# TeensyLED_15061000.net
KiCad netlist of a schematic drawn in EAGLE
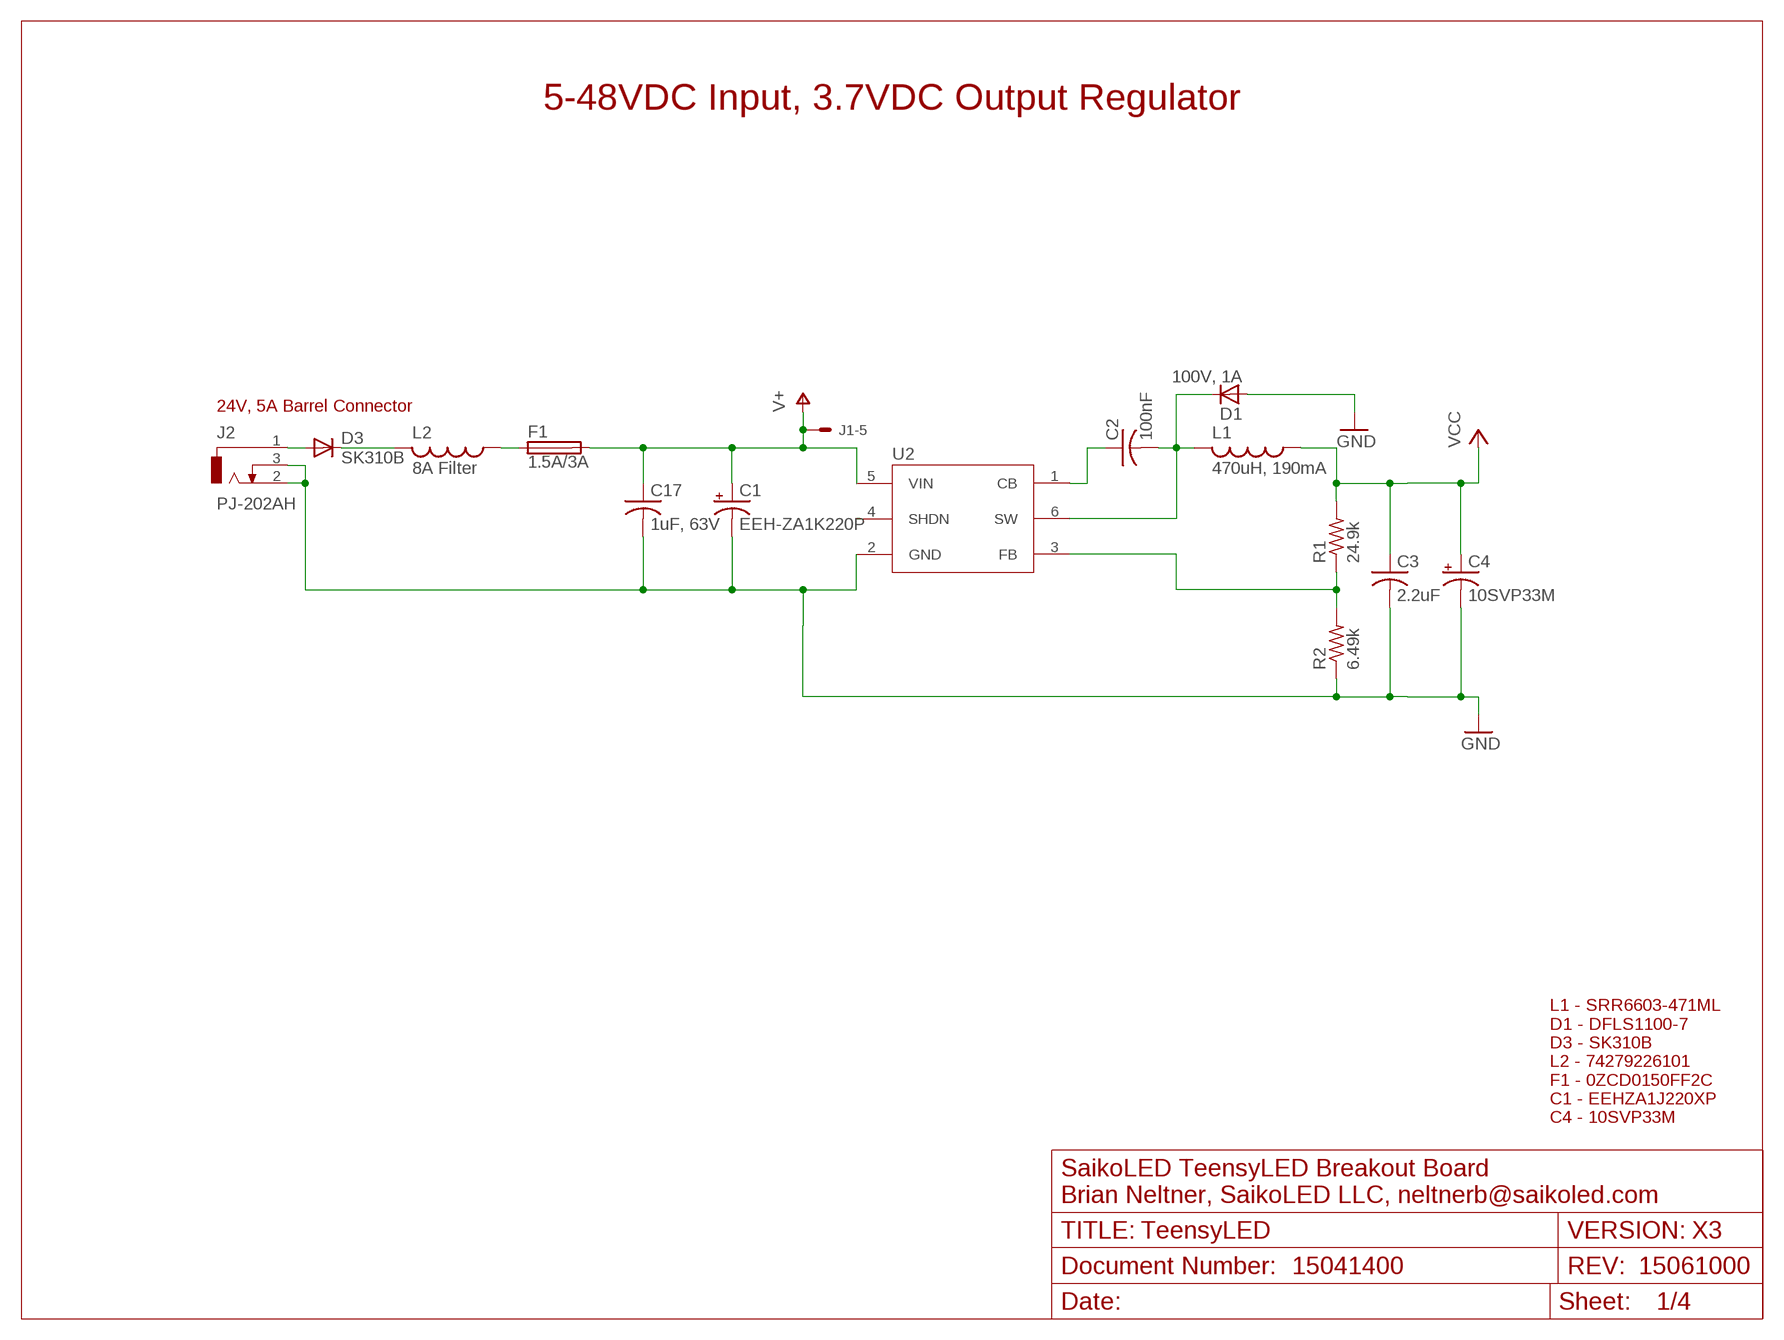
[diagram p0: schematic, sheet 1]
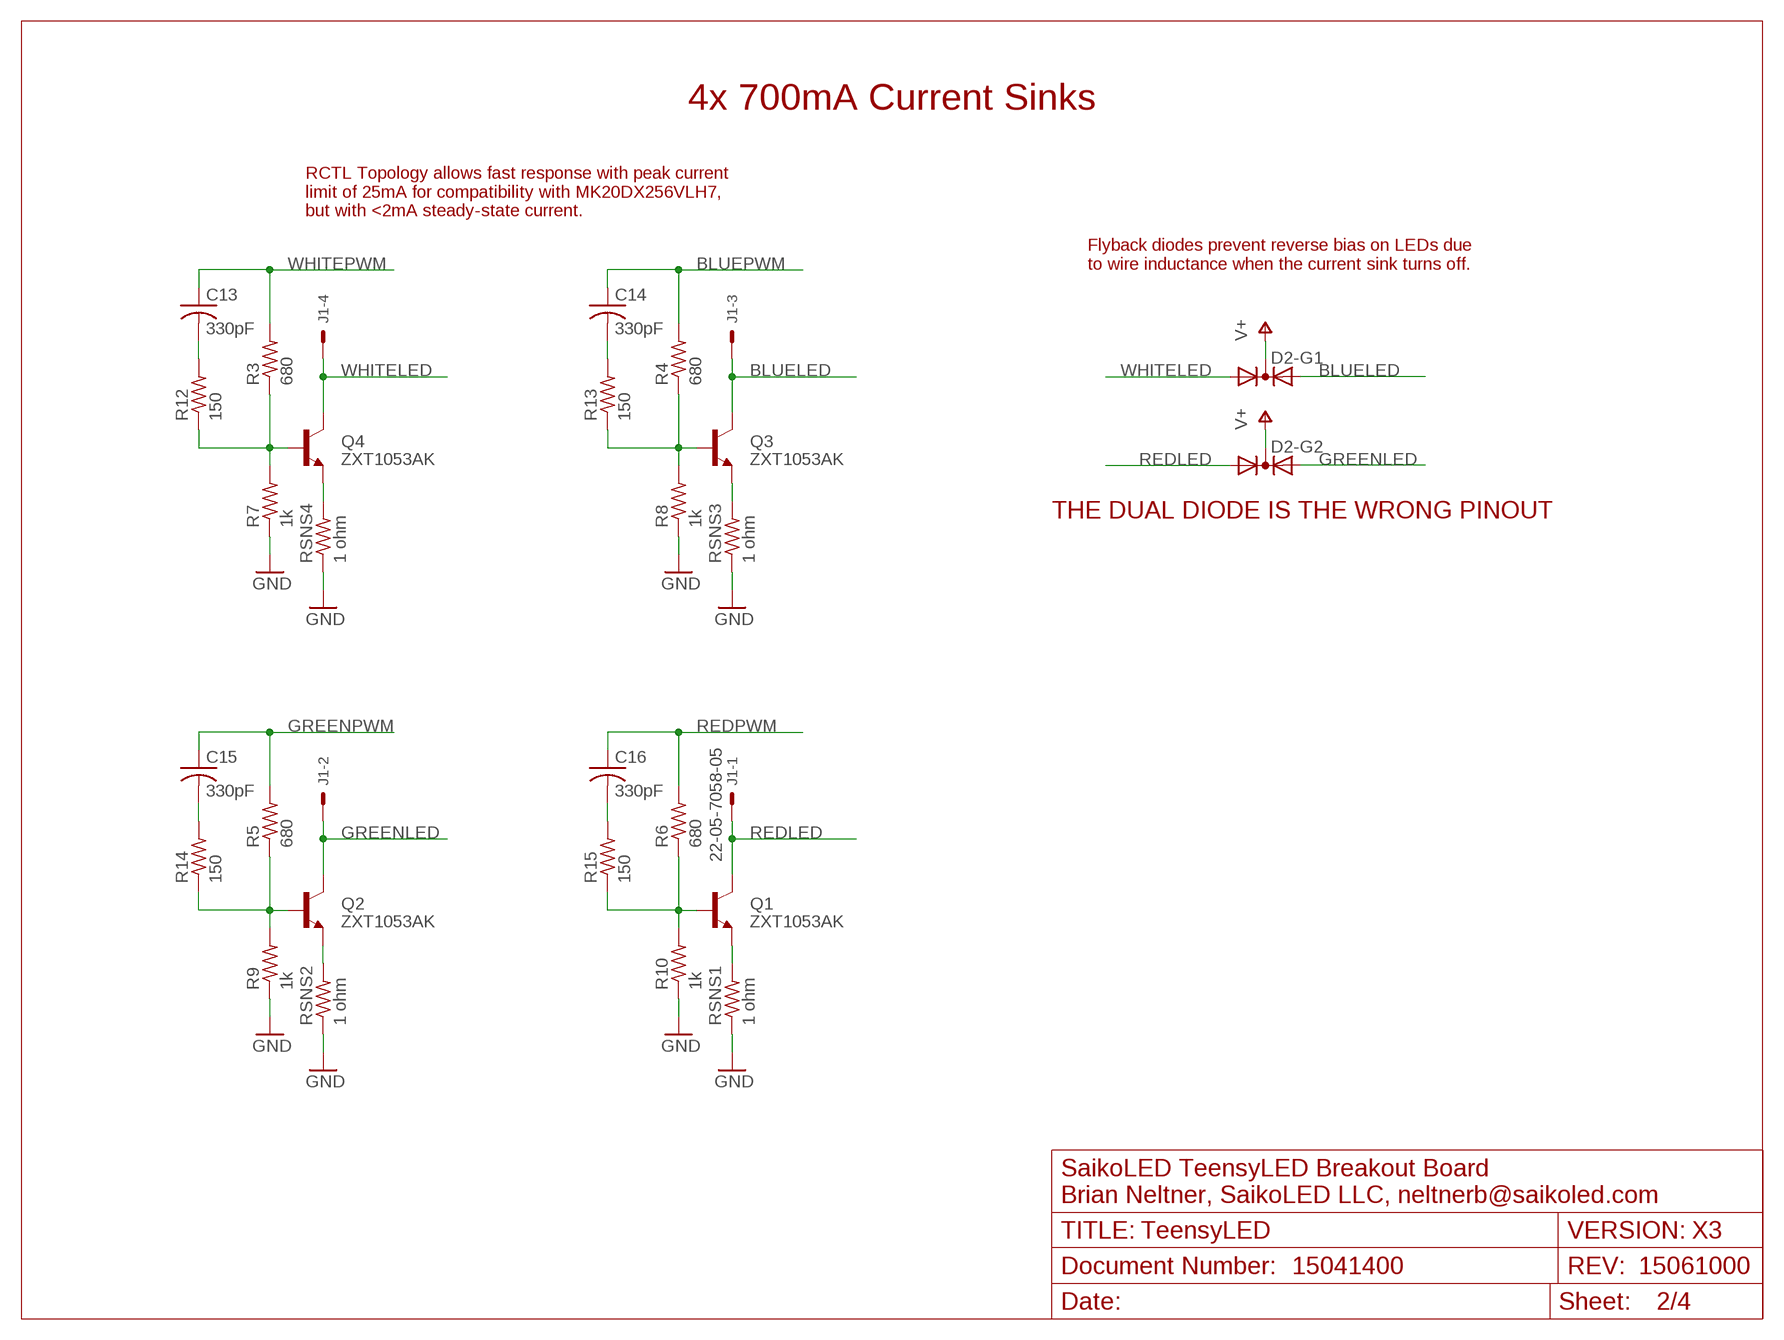
[diagram p1: schematic, sheet 2]
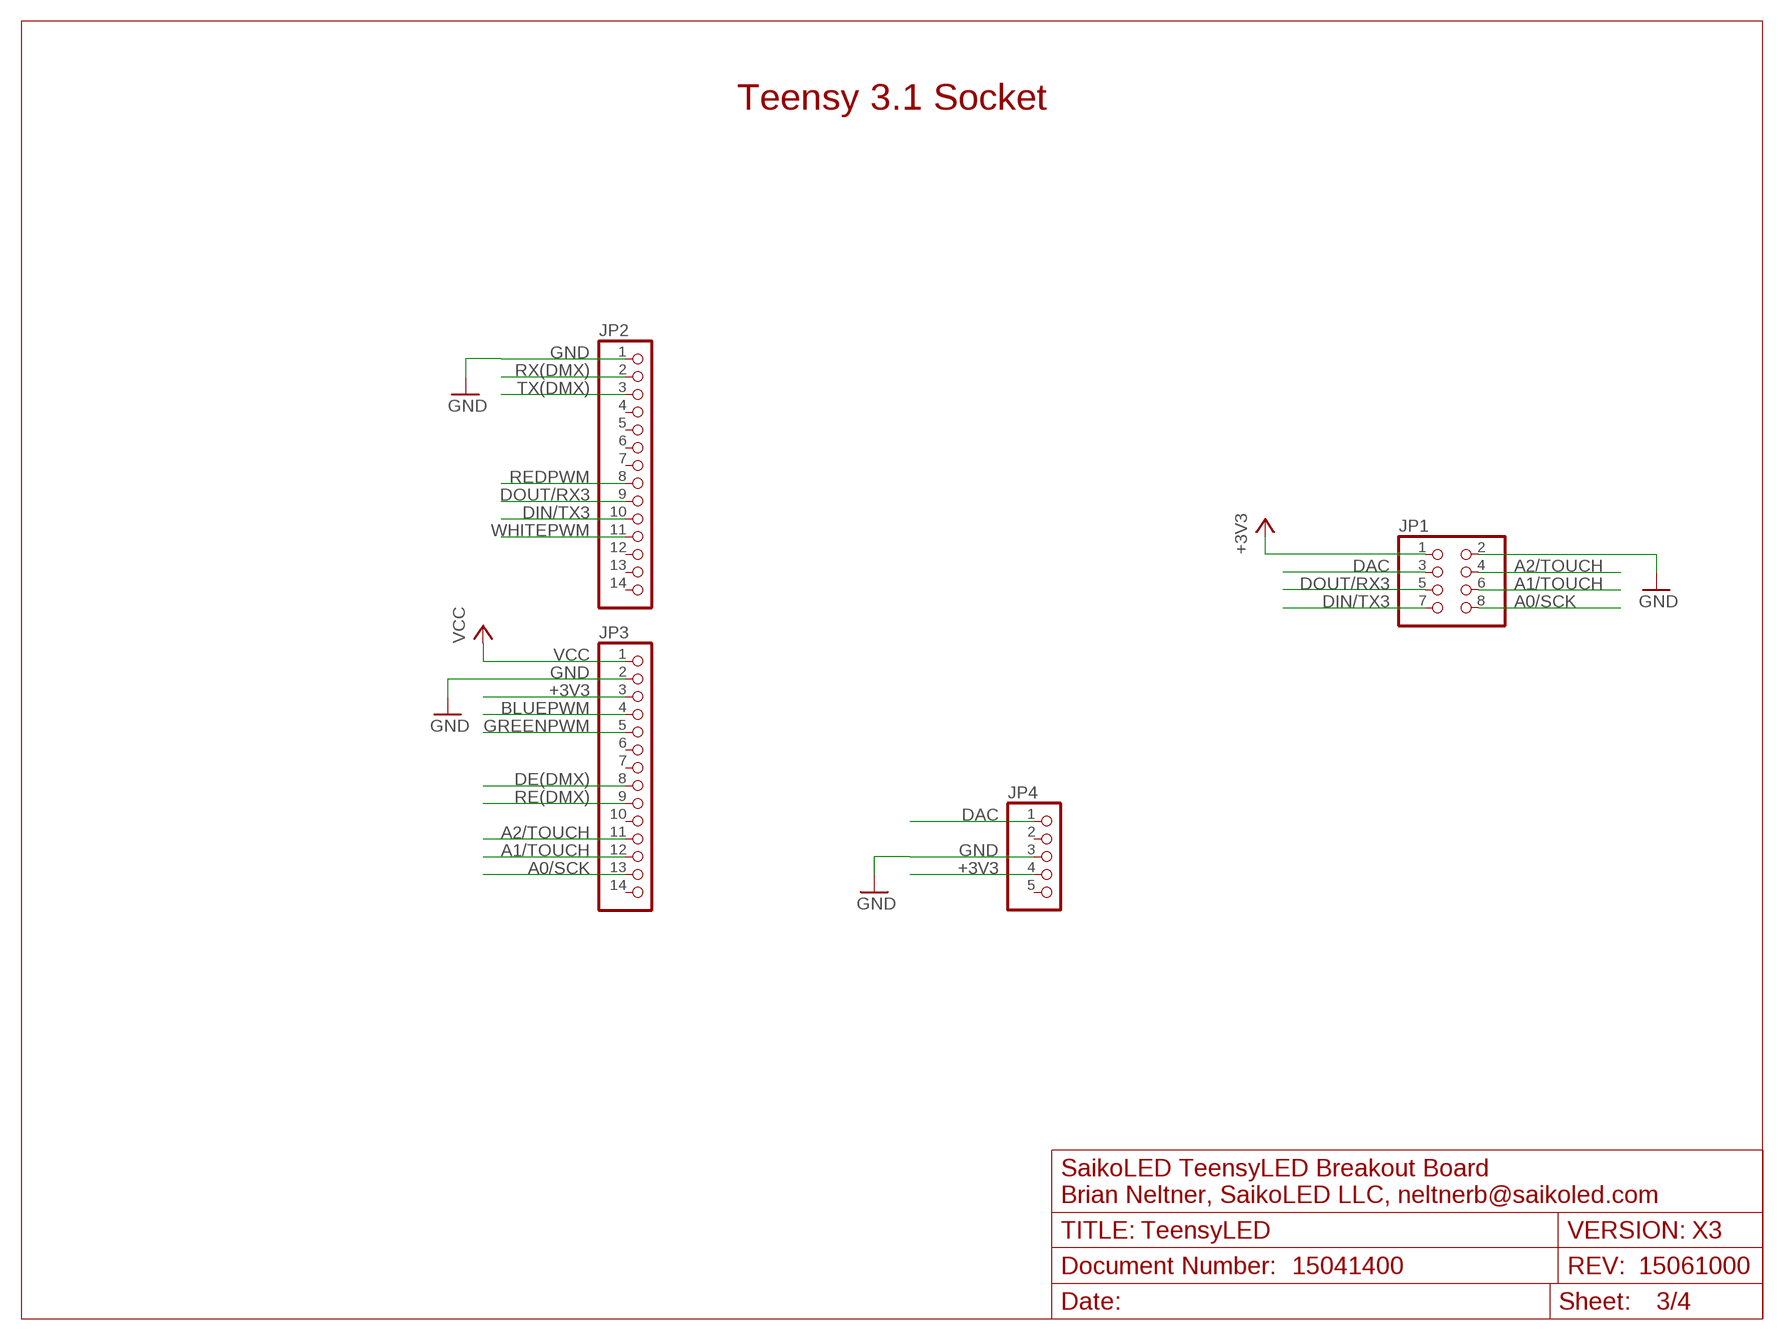
[diagram p2: schematic, sheet 3]
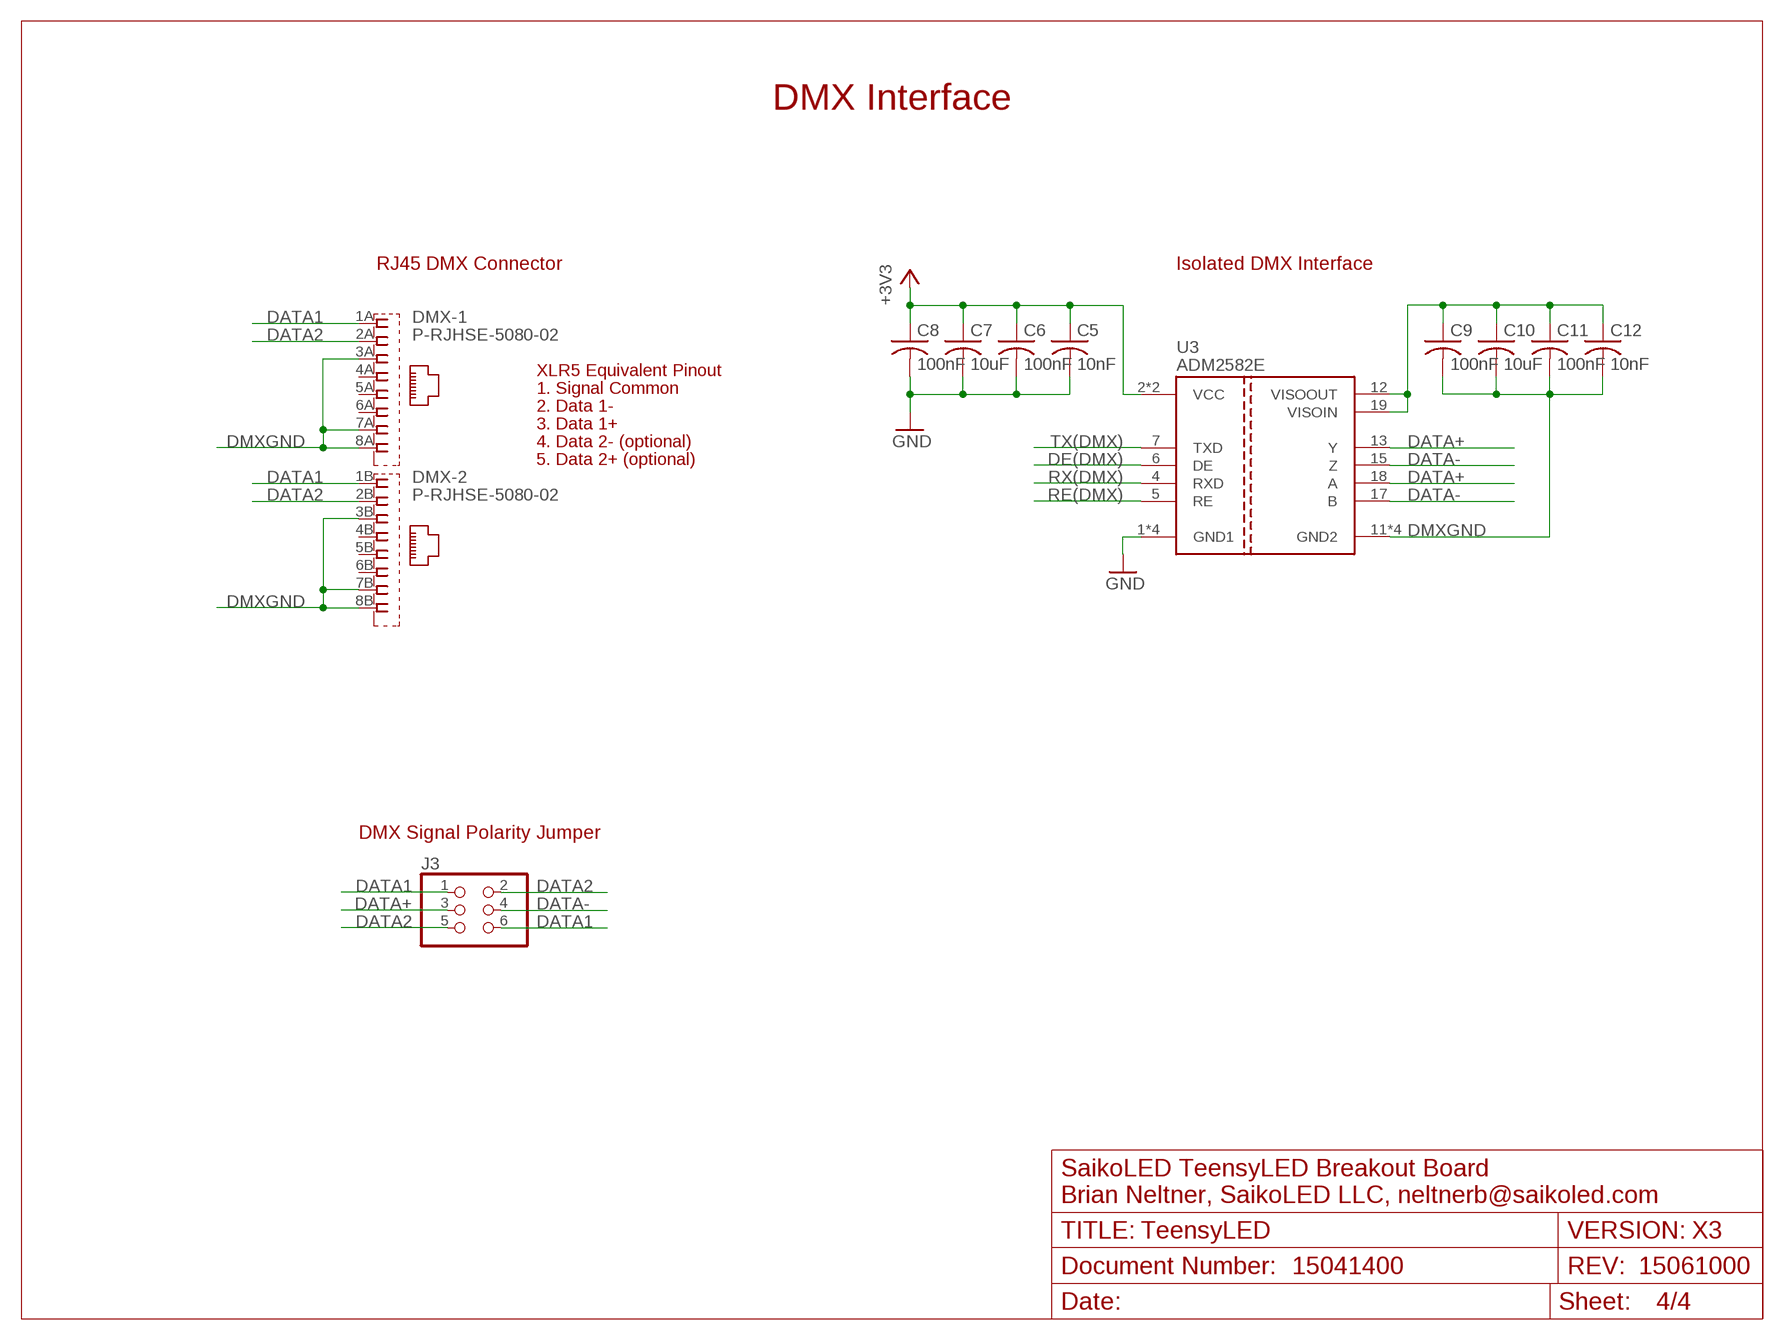
[diagram p3: schematic, sheet 4]

(export (version "E")
  (design (tool "Eeschema 10.0.6"))
  (components
    (comp (ref "C5")
      (value "10nF")
      (footprint "eagle-import:C0402PRO")
      (libsource (lib "eagle-import") (part "C-USC0402PRO"))
    )
    (comp (ref "C6")
      (value "100nF")
      (footprint "eagle-import:C0402PRO")
      (libsource (lib "eagle-import") (part "C-USC0402PRO"))
    )
    (comp (ref "C7")
      (value "10uF")
      (footprint "eagle-import:C0402PRO")
      (libsource (lib "eagle-import") (part "C-USC0402PRO"))
    )
    (comp (ref "C8")
      (value "100nF")
      (footprint "eagle-import:C0402PRO")
      (libsource (lib "eagle-import") (part "C-USC0402PRO"))
    )
    (comp (ref "C9")
      (value "100nF")
      (footprint "eagle-import:C0402PRO")
      (libsource (lib "eagle-import") (part "C-USC0402PRO"))
    )
    (comp (ref "C10")
      (value "10uF")
      (footprint "eagle-import:C0402PRO")
      (libsource (lib "eagle-import") (part "C-USC0402PRO"))
    )
    (comp (ref "C11")
      (value "100nF")
      (footprint "eagle-import:C0402PRO")
      (libsource (lib "eagle-import") (part "C-USC0402PRO"))
    )
    (comp (ref "C12")
      (value "10nF")
      (footprint "eagle-import:C0402PRO")
      (libsource (lib "eagle-import") (part "C-USC0402PRO"))
    )
    (comp (ref "DMX")
      (value "P-RJHSE-5080-02")
      (footprint "eagle-import:P-RJHSE-5080-02")
      (libsource (lib "eagle-import") (part "P-RJHSE-5080-02"))
    )
    (comp (ref "FRAME4")
      (value "LETTER_LNOSILK")
      (footprint "eagle-import:EMPTY")
      (libsource (lib "eagle-import") (part "LETTER_LNOSILK"))
    )
    (comp (ref "J3")
      (value "PINHD-2X3")
      (footprint "eagle-import:2X03")
      (libsource (lib "eagle-import") (part "PINHD-2X3"))
    )
    (comp (ref "U3")
      (value "ADM2582E")
      (footprint "eagle-import:SO-20DW")
      (libsource (lib "eagle-import") (part "ADM2582E"))
    )
    (comp (ref "C1")
      (value "EEH-ZA1K220P")
      (footprint "eagle-import:PANASONIC_F")
      (libsource (lib "eagle-import") (part "CPOL-USF"))
    )
    (comp (ref "C2")
      (value "100nF")
      (footprint "eagle-import:C0805K")
      (libsource (lib "eagle-import") (part "C-USC0805K"))
    )
    (comp (ref "C3")
      (value "2.2uF")
      (footprint "eagle-import:C0402PRO")
      (fields (field (name "MF") "Multicomp Passives") (field (name "MPN") "MCLV4R7M1HB-0513-RH"))
      (libsource (lib "eagle-import") (part "C-USC0402PRO"))
    )
    (comp (ref "C4")
      (value "10SVP33M")
      (footprint "eagle-import:PANASONIC_B")
      (libsource (lib "eagle-import") (part "CPOL-USB"))
    )
    (comp (ref "C17")
      (value "1uF, 63V")
      (footprint "eagle-import:C0805K")
      (fields (field (name "MF") "Multicomp Passives") (field (name "MPN") "MCLV4R7M1HB-0513-RH"))
      (libsource (lib "eagle-import") (part "C-USC0805K"))
    )
    (comp (ref "D1")
      (value "100V, 1A")
      (footprint "eagle-import:DFLS1100")
      (libsource (lib "eagle-import") (part "DFLS1100"))
    )
    (comp (ref "D3")
      (value "SK310B")
      (footprint "eagle-import:SMB")
      (libsource (lib "eagle-import") (part "DIODE-SMB"))
    )
    (comp (ref "F1")
      (value "1.5A/3A")
      (footprint "eagle-import:2920")
      (libsource (lib "eagle-import") (part "PTCFUSE-0ZCD"))
    )
    (comp (ref "FRAME1")
      (value "LETTER_LNOSILK")
      (footprint "eagle-import:EMPTY")
      (libsource (lib "eagle-import") (part "LETTER_LNOSILK"))
    )
    (comp (ref "J1")
      (value "22-05-7058-05")
      (footprint "eagle-import:7395-05")
      (libsource (lib "eagle-import") (part "22-?-0505-7058"))
    )
    (comp (ref "J2")
      (value "PJ-202AH")
      (footprint "eagle-import:PJ-202AH")
      (libsource (lib "eagle-import") (part "PJ-202AH"))
    )
    (comp (ref "L1")
      (value "470uH, 190mA")
      (footprint "eagle-import:SRR6603")
      (libsource (lib "eagle-import") (part "L-US-SRR6603"))
    )
    (comp (ref "L2")
      (value "8A Filter")
      (footprint "eagle-import:L1812")
      (libsource (lib "eagle-import") (part "L-USL1812"))
    )
    (comp (ref "R1")
      (value "24.9k")
      (footprint "eagle-import:R0402PRO")
      (fields (field (name "MPN") "BLU0402-9762-BT25W"))
      (libsource (lib "eagle-import") (part "R-US_R0402PRO"))
    )
    (comp (ref "R2")
      (value "6.49k")
      (footprint "eagle-import:R0402PRO")
      (fields (field (name "MPN") "ERJ-3EKF4123V"))
      (libsource (lib "eagle-import") (part "R-US_R0402PRO"))
    )
    (comp (ref "U2")
      (value "LMR16006YDDCT")
      (footprint "eagle-import:DDC0006A")
      (fields
        (field (name "MANUFACTURER") "Texas Instruments")
        (field (name "PARTNUMBER") "LMR16006YDDC")
        (field (name "MF") "FARNELL")
      )
      (libsource (lib "eagle-import") (part "LMR16006YDDCT"))
    )
    (comp (ref "FRAME3")
      (value "LETTER_LNOSILK")
      (footprint "eagle-import:EMPTY")
      (libsource (lib "eagle-import") (part "LETTER_LNOSILK"))
    )
    (comp (ref "JP1")
      (value "PINHD-2X4")
      (footprint "eagle-import:2X04")
      (libsource (lib "eagle-import") (part "PINHD-2X4"))
    )
    (comp (ref "JP2")
      (value "PINHD-1X14/ROUND")
      (footprint "eagle-import:1X14_ROUND")
      (libsource (lib "eagle-import") (part "PINHD-1X14/ROUND"))
    )
    (comp (ref "JP3")
      (value "PINHD-1X14/ROUND")
      (footprint "eagle-import:1X14_ROUND")
      (libsource (lib "eagle-import") (part "PINHD-1X14/ROUND"))
    )
    (comp (ref "JP4")
      (value "PINHD-1X5/ROUND")
      (footprint "eagle-import:1X05_ROUND")
      (libsource (lib "eagle-import") (part "PINHD-1X5/ROUND"))
    )
    (comp (ref "C13")
      (value "330pF")
      (footprint "eagle-import:C0402PRO")
      (libsource (lib "eagle-import") (part "C-USC0402PRO"))
    )
    (comp (ref "C14")
      (value "330pF")
      (footprint "eagle-import:C0402PRO")
      (libsource (lib "eagle-import") (part "C-USC0402PRO"))
    )
    (comp (ref "C15")
      (value "330pF")
      (footprint "eagle-import:C0402PRO")
      (libsource (lib "eagle-import") (part "C-USC0402PRO"))
    )
    (comp (ref "C16")
      (value "330pF")
      (footprint "eagle-import:C0402PRO")
      (libsource (lib "eagle-import") (part "C-USC0402PRO"))
    )
    (comp (ref "D2")
      (value "DUAL_DIODE_AC-CA-SOT363")
      (footprint "eagle-import:SOT363_PHILIPS")
      (libsource (lib "eagle-import") (part "DUAL_DIODE_AC-CA-SOT363"))
    )
    (comp (ref "FRAME2")
      (value "LETTER_LNOSILK")
      (footprint "eagle-import:EMPTY")
      (libsource (lib "eagle-import") (part "LETTER_LNOSILK"))
    )
    (comp (ref "Q1")
      (value "ZXT1053AK")
      (footprint "eagle-import:TO252")
      (libsource (lib "eagle-import") (part "ZXT1053AK"))
    )
    (comp (ref "Q2")
      (value "ZXT1053AK")
      (footprint "eagle-import:TO252")
      (libsource (lib "eagle-import") (part "ZXT1053AK"))
    )
    (comp (ref "Q3")
      (value "ZXT1053AK")
      (footprint "eagle-import:TO252")
      (libsource (lib "eagle-import") (part "ZXT1053AK"))
    )
    (comp (ref "Q4")
      (value "ZXT1053AK")
      (footprint "eagle-import:TO252")
      (libsource (lib "eagle-import") (part "ZXT1053AK"))
    )
    (comp (ref "R3")
      (value "680")
      (footprint "eagle-import:R0402PRO")
      (libsource (lib "eagle-import") (part "R-US_R0402PRO"))
    )
    (comp (ref "R4")
      (value "680")
      (footprint "eagle-import:R0402PRO")
      (libsource (lib "eagle-import") (part "R-US_R0402PRO"))
    )
    (comp (ref "R5")
      (value "680")
      (footprint "eagle-import:R0402PRO")
      (libsource (lib "eagle-import") (part "R-US_R0402PRO"))
    )
    (comp (ref "R6")
      (value "680")
      (footprint "eagle-import:R0402PRO")
      (libsource (lib "eagle-import") (part "R-US_R0402PRO"))
    )
    (comp (ref "R7")
      (value "1k")
      (footprint "eagle-import:R0402PRO")
      (libsource (lib "eagle-import") (part "R-US_R0402PRO"))
    )
    (comp (ref "R8")
      (value "1k")
      (footprint "eagle-import:R0402PRO")
      (libsource (lib "eagle-import") (part "R-US_R0402PRO"))
    )
    (comp (ref "R9")
      (value "1k")
      (footprint "eagle-import:R0402PRO")
      (libsource (lib "eagle-import") (part "R-US_R0402PRO"))
    )
    (comp (ref "R10")
      (value "1k")
      (footprint "eagle-import:R0402PRO")
      (libsource (lib "eagle-import") (part "R-US_R0402PRO"))
    )
    (comp (ref "R12")
      (value "150")
      (footprint "eagle-import:R0402PRO")
      (libsource (lib "eagle-import") (part "R-US_R0402PRO"))
    )
    (comp (ref "R13")
      (value "150")
      (footprint "eagle-import:R0402PRO")
      (libsource (lib "eagle-import") (part "R-US_R0402PRO"))
    )
    (comp (ref "R14")
      (value "150")
      (footprint "eagle-import:R0402PRO")
      (libsource (lib "eagle-import") (part "R-US_R0402PRO"))
    )
    (comp (ref "R15")
      (value "150")
      (footprint "eagle-import:R0402PRO")
      (libsource (lib "eagle-import") (part "R-US_R0402PRO"))
    )
    (comp (ref "RSNS1")
      (value "1 ohm")
      (footprint "eagle-import:R1206")
      (libsource (lib "eagle-import") (part "R-US_R1206"))
    )
    (comp (ref "RSNS2")
      (value "1 ohm")
      (footprint "eagle-import:R1206")
      (libsource (lib "eagle-import") (part "R-US_R1206"))
    )
    (comp (ref "RSNS3")
      (value "1 ohm")
      (footprint "eagle-import:R1206")
      (libsource (lib "eagle-import") (part "R-US_R1206"))
    )
    (comp (ref "RSNS4")
      (value "1 ohm")
      (footprint "eagle-import:R1206")
      (libsource (lib "eagle-import") (part "R-US_R1206"))
    )
  )
  (nets
    (net (code "1") (name "+3V3") (class "Default")
      (node (ref "C5") (pin "1") (pinfunction "1_1") (pintype "passive"))
      (node (ref "C6") (pin "1") (pinfunction "1_1") (pintype "passive"))
      (node (ref "C7") (pin "1") (pinfunction "1_1") (pintype "passive"))
      (node (ref "C8") (pin "1") (pinfunction "1_1") (pintype "passive"))
      (node (ref "JP1") (pin "1") (pinfunction "1_1") (pintype "passive"))
      (node (ref "JP3") (pin "3") (pinfunction "3_3") (pintype "passive"))
      (node (ref "JP4") (pin "4") (pinfunction "4_4") (pintype "passive"))
      (node (ref "U3") (pin "2") (pinfunction "VCC_2") (pintype "bidirectional"))
      (node (ref "U3") (pin "8") (pinfunction "VCC_8") (pintype "bidirectional"))
    )
    (net (code "2") (name "A0{slash}SCK") (class "Default")
      (node (ref "JP1") (pin "8") (pinfunction "8_8") (pintype "passive"))
      (node (ref "JP3") (pin "13") (pinfunction "13_13") (pintype "passive"))
    )
    (net (code "3") (name "A1{slash}TOUCH") (class "Default")
      (node (ref "JP1") (pin "6") (pinfunction "6_6") (pintype "passive"))
      (node (ref "JP3") (pin "12") (pinfunction "12_12") (pintype "passive"))
    )
    (net (code "4") (name "A2{slash}TOUCH") (class "Default")
      (node (ref "JP1") (pin "4") (pinfunction "4_4") (pintype "passive"))
      (node (ref "JP3") (pin "11") (pinfunction "11_11") (pintype "passive"))
    )
    (net (code "5") (name "BLUELED") (class "Default")
      (node (ref "D2") (pin "3") (pinfunction "A2_3") (pintype "passive"))
      (node (ref "J1") (pin "3") (pinfunction "S_3") (pintype "passive"))
      (node (ref "Q3") (pin "C") (pinfunction "C_C") (pintype "passive"))
    )
    (net (code "6") (name "BLUEPWM") (class "Default")
      (node (ref "C14") (pin "1") (pinfunction "1_1") (pintype "passive"))
      (node (ref "JP3") (pin "4") (pinfunction "4_4") (pintype "passive"))
      (node (ref "R4") (pin "2") (pinfunction "2_2") (pintype "passive"))
    )
    (net (code "7") (name "DAC") (class "Default")
      (node (ref "JP1") (pin "3") (pinfunction "3_3") (pintype "passive"))
      (node (ref "JP4") (pin "1") (pinfunction "1_1") (pintype "passive"))
    )
    (net (code "8") (name "DATA+") (class "Default")
      (node (ref "J3") (pin "3") (pinfunction "3_3") (pintype "passive"))
      (node (ref "U3") (pin "13") (pinfunction "Y_13") (pintype "bidirectional"))
      (node (ref "U3") (pin "18") (pinfunction "A_18") (pintype "bidirectional"))
    )
    (net (code "9") (name "DATA-") (class "Default")
      (node (ref "J3") (pin "4") (pinfunction "4_4") (pintype "passive"))
      (node (ref "U3") (pin "15") (pinfunction "Z_15") (pintype "bidirectional"))
      (node (ref "U3") (pin "17") (pinfunction "B_17") (pintype "bidirectional"))
    )
    (net (code "10") (name "DATA1") (class "Default")
      (node (ref "DMX") (pin "1A") (pinfunction "1_1A") (pintype "passive"))
      (node (ref "DMX") (pin "1B") (pinfunction "1_1B") (pintype "passive"))
      (node (ref "J3") (pin "1") (pinfunction "1_1") (pintype "passive"))
      (node (ref "J3") (pin "6") (pinfunction "6_6") (pintype "passive"))
    )
    (net (code "11") (name "DATA2") (class "Default")
      (node (ref "DMX") (pin "2A") (pinfunction "2_2A") (pintype "passive"))
      (node (ref "DMX") (pin "2B") (pinfunction "2_2B") (pintype "passive"))
      (node (ref "J3") (pin "2") (pinfunction "2_2") (pintype "passive"))
      (node (ref "J3") (pin "5") (pinfunction "5_5") (pintype "passive"))
    )
    (net (code "12") (name "DE(DMX)") (class "Default")
      (node (ref "JP3") (pin "8") (pinfunction "8_8") (pintype "passive"))
      (node (ref "U3") (pin "6") (pinfunction "DE_6") (pintype "bidirectional"))
    )
    (net (code "13") (name "DIN{slash}TX3") (class "Default")
      (node (ref "JP1") (pin "7") (pinfunction "7_7") (pintype "passive"))
      (node (ref "JP2") (pin "10") (pinfunction "10_10") (pintype "passive"))
    )
    (net (code "14") (name "DMXGND") (class "Default")
      (node (ref "C10") (pin "2") (pinfunction "2_2") (pintype "passive"))
      (node (ref "C11") (pin "2") (pinfunction "2_2") (pintype "passive"))
      (node (ref "C12") (pin "2") (pinfunction "2_2") (pintype "passive"))
      (node (ref "C9") (pin "2") (pinfunction "2_2") (pintype "passive"))
      (node (ref "DMX") (pin "3A") (pinfunction "3_3A") (pintype "passive"))
      (node (ref "DMX") (pin "3B") (pinfunction "3_3B") (pintype "passive"))
      (node (ref "DMX") (pin "7A") (pinfunction "7_7A") (pintype "passive"))
      (node (ref "DMX") (pin "7B") (pinfunction "7_7B") (pintype "passive"))
      (node (ref "DMX") (pin "8A") (pinfunction "8_8A") (pintype "passive"))
      (node (ref "DMX") (pin "8B") (pinfunction "8_8B") (pintype "passive"))
      (node (ref "U3") (pin "11") (pinfunction "GND2_11") (pintype "bidirectional"))
      (node (ref "U3") (pin "14") (pinfunction "GND2_14") (pintype "bidirectional"))
      (node (ref "U3") (pin "16") (pinfunction "GND2_16") (pintype "bidirectional"))
      (node (ref "U3") (pin "20") (pinfunction "GND2_20") (pintype "bidirectional"))
    )
    (net (code "15") (name "DOUT{slash}RX3") (class "Default")
      (node (ref "JP1") (pin "5") (pinfunction "5_5") (pintype "passive"))
      (node (ref "JP2") (pin "9") (pinfunction "9_9") (pintype "passive"))
    )
    (net (code "16") (name "GND") (class "Default")
      (node (ref "C1") (pin "-") (pinfunction "-_-") (pintype "passive"))
      (node (ref "C17") (pin "2") (pinfunction "2_2") (pintype "passive"))
      (node (ref "C3") (pin "2") (pinfunction "2_2") (pintype "passive"))
      (node (ref "C4") (pin "-") (pinfunction "-_-") (pintype "passive"))
      (node (ref "C5") (pin "2") (pinfunction "2_2") (pintype "passive"))
      (node (ref "C6") (pin "2") (pinfunction "2_2") (pintype "passive"))
      (node (ref "C7") (pin "2") (pinfunction "2_2") (pintype "passive"))
      (node (ref "C8") (pin "2") (pinfunction "2_2") (pintype "passive"))
      (node (ref "D1") (pin "A") (pinfunction "A_A") (pintype "passive"))
      (node (ref "J2") (pin "2") (pinfunction "3_2") (pintype "passive"))
      (node (ref "J2") (pin "3") (pinfunction "2_3") (pintype "passive"))
      (node (ref "JP1") (pin "2") (pinfunction "2_2") (pintype "passive"))
      (node (ref "JP2") (pin "1") (pinfunction "1_1") (pintype "passive"))
      (node (ref "JP3") (pin "2") (pinfunction "2_2") (pintype "passive"))
      (node (ref "JP4") (pin "3") (pinfunction "3_3") (pintype "passive"))
      (node (ref "R10") (pin "1") (pinfunction "1_1") (pintype "passive"))
      (node (ref "R2") (pin "1") (pinfunction "1_1") (pintype "passive"))
      (node (ref "R7") (pin "1") (pinfunction "1_1") (pintype "passive"))
      (node (ref "R8") (pin "1") (pinfunction "1_1") (pintype "passive"))
      (node (ref "R9") (pin "1") (pinfunction "1_1") (pintype "passive"))
      (node (ref "RSNS1") (pin "1") (pinfunction "1_1") (pintype "passive"))
      (node (ref "RSNS2") (pin "1") (pinfunction "1_1") (pintype "passive"))
      (node (ref "RSNS3") (pin "1") (pinfunction "1_1") (pintype "passive"))
      (node (ref "RSNS4") (pin "1") (pinfunction "1_1") (pintype "passive"))
      (node (ref "U2") (pin "2") (pinfunction "GND_2") (pintype "power_in"))
      (node (ref "U3") (pin "1") (pinfunction "GND1_1") (pintype "bidirectional"))
      (node (ref "U3") (pin "10") (pinfunction "GND1_10") (pintype "bidirectional"))
      (node (ref "U3") (pin "3") (pinfunction "GND1_3") (pintype "bidirectional"))
      (node (ref "U3") (pin "9") (pinfunction "GND1_9") (pintype "bidirectional"))
    )
    (net (code "17") (name "GREENLED") (class "Default")
      (node (ref "D2") (pin "4") (pinfunction "A2_4") (pintype "passive"))
      (node (ref "J1") (pin "2") (pinfunction "S_2") (pintype "passive"))
      (node (ref "Q2") (pin "C") (pinfunction "C_C") (pintype "passive"))
    )
    (net (code "18") (name "GREENPWM") (class "Default")
      (node (ref "C15") (pin "1") (pinfunction "1_1") (pintype "passive"))
      (node (ref "JP3") (pin "5") (pinfunction "5_5") (pintype "passive"))
      (node (ref "R5") (pin "2") (pinfunction "2_2") (pintype "passive"))
    )
    (net (code "19") (name "Net-(C13-Pad2)") (class "Default")
      (node (ref "C13") (pin "2") (pinfunction "2_2") (pintype "passive"))
      (node (ref "R12") (pin "2") (pinfunction "2_2") (pintype "passive"))
    )
    (net (code "20") (name "Net-(C14-Pad2)") (class "Default")
      (node (ref "C14") (pin "2") (pinfunction "2_2") (pintype "passive"))
      (node (ref "R13") (pin "2") (pinfunction "2_2") (pintype "passive"))
    )
    (net (code "21") (name "Net-(C15-Pad2)") (class "Default")
      (node (ref "C15") (pin "2") (pinfunction "2_2") (pintype "passive"))
      (node (ref "R14") (pin "2") (pinfunction "2_2") (pintype "passive"))
    )
    (net (code "22") (name "Net-(C16-Pad2)") (class "Default")
      (node (ref "C16") (pin "2") (pinfunction "2_2") (pintype "passive"))
      (node (ref "R15") (pin "2") (pinfunction "2_2") (pintype "passive"))
    )
    (net (code "23") (name "Net-(D3-PadA)") (class "Default")
      (node (ref "D3") (pin "A") (pinfunction "A_A") (pintype "passive"))
      (node (ref "J2") (pin "1") (pinfunction "1_1") (pintype "passive"))
    )
    (net (code "24") (name "Net-(D3-PadC)") (class "Default")
      (node (ref "D3") (pin "C") (pinfunction "C_C") (pintype "passive"))
      (node (ref "L2") (pin "2") (pinfunction "2_2") (pintype "passive"))
    )
    (net (code "25") (name "Net-(F1-1)") (class "Default")
      (node (ref "F1") (pin "P$1") (pinfunction "1_P$1") (pintype "passive"))
      (node (ref "L2") (pin "1") (pinfunction "1_1") (pintype "passive"))
    )
    (net (code "26") (name "Net-(L1-2)") (class "Default")
      (node (ref "C2") (pin "2") (pinfunction "2_2") (pintype "passive"))
      (node (ref "D1") (pin "C") (pinfunction "C_C") (pintype "passive"))
      (node (ref "L1") (pin "P$2") (pinfunction "2_P$2") (pintype "passive"))
      (node (ref "U2") (pin "6") (pinfunction "SW_6") (pintype "power_in"))
    )
    (net (code "27") (name "Net-(Q1-PadB)") (class "Default")
      (node (ref "Q1") (pin "B") (pinfunction "B_B") (pintype "passive"))
      (node (ref "R10") (pin "2") (pinfunction "2_2") (pintype "passive"))
      (node (ref "R15") (pin "1") (pinfunction "1_1") (pintype "passive"))
      (node (ref "R6") (pin "1") (pinfunction "1_1") (pintype "passive"))
    )
    (net (code "28") (name "Net-(Q1-PadE)") (class "Default")
      (node (ref "Q1") (pin "E") (pinfunction "E_E") (pintype "passive"))
      (node (ref "RSNS1") (pin "2") (pinfunction "2_2") (pintype "passive"))
    )
    (net (code "29") (name "Net-(Q2-PadB)") (class "Default")
      (node (ref "Q2") (pin "B") (pinfunction "B_B") (pintype "passive"))
      (node (ref "R14") (pin "1") (pinfunction "1_1") (pintype "passive"))
      (node (ref "R5") (pin "1") (pinfunction "1_1") (pintype "passive"))
      (node (ref "R9") (pin "2") (pinfunction "2_2") (pintype "passive"))
    )
    (net (code "30") (name "Net-(Q2-PadE)") (class "Default")
      (node (ref "Q2") (pin "E") (pinfunction "E_E") (pintype "passive"))
      (node (ref "RSNS2") (pin "2") (pinfunction "2_2") (pintype "passive"))
    )
    (net (code "31") (name "Net-(Q3-PadB)") (class "Default")
      (node (ref "Q3") (pin "B") (pinfunction "B_B") (pintype "passive"))
      (node (ref "R13") (pin "1") (pinfunction "1_1") (pintype "passive"))
      (node (ref "R4") (pin "1") (pinfunction "1_1") (pintype "passive"))
      (node (ref "R8") (pin "2") (pinfunction "2_2") (pintype "passive"))
    )
    (net (code "32") (name "Net-(Q3-PadE)") (class "Default")
      (node (ref "Q3") (pin "E") (pinfunction "E_E") (pintype "passive"))
      (node (ref "RSNS3") (pin "2") (pinfunction "2_2") (pintype "passive"))
    )
    (net (code "33") (name "Net-(Q4-PadB)") (class "Default")
      (node (ref "Q4") (pin "B") (pinfunction "B_B") (pintype "passive"))
      (node (ref "R12") (pin "1") (pinfunction "1_1") (pintype "passive"))
      (node (ref "R3") (pin "1") (pinfunction "1_1") (pintype "passive"))
      (node (ref "R7") (pin "2") (pinfunction "2_2") (pintype "passive"))
    )
    (net (code "34") (name "Net-(Q4-PadE)") (class "Default")
      (node (ref "Q4") (pin "E") (pinfunction "E_E") (pintype "passive"))
      (node (ref "RSNS4") (pin "2") (pinfunction "2_2") (pintype "passive"))
    )
    (net (code "35") (name "Net-(U2-CB)") (class "Default")
      (node (ref "C2") (pin "1") (pinfunction "1_1") (pintype "passive"))
      (node (ref "U2") (pin "1") (pinfunction "CB_1") (pintype "output"))
    )
    (net (code "36") (name "Net-(U2-FB)") (class "Default")
      (node (ref "R1") (pin "1") (pinfunction "1_1") (pintype "passive"))
      (node (ref "R2") (pin "2") (pinfunction "2_2") (pintype "passive"))
      (node (ref "U2") (pin "3") (pinfunction "FB_3") (pintype "input"))
    )
    (net (code "37") (name "Net-(U3-VISOIN)") (class "Default")
      (node (ref "C10") (pin "1") (pinfunction "1_1") (pintype "passive"))
      (node (ref "C11") (pin "1") (pinfunction "1_1") (pintype "passive"))
      (node (ref "C12") (pin "1") (pinfunction "1_1") (pintype "passive"))
      (node (ref "C9") (pin "1") (pinfunction "1_1") (pintype "passive"))
      (node (ref "U3") (pin "12") (pinfunction "VISOOUT_12") (pintype "bidirectional"))
      (node (ref "U3") (pin "19") (pinfunction "VISOIN_19") (pintype "bidirectional"))
    )
    (net (code "38") (name "RE(DMX)") (class "Default")
      (node (ref "JP3") (pin "9") (pinfunction "9_9") (pintype "passive"))
      (node (ref "U3") (pin "5") (pinfunction "RE_5") (pintype "bidirectional"))
    )
    (net (code "39") (name "REDLED") (class "Default")
      (node (ref "D2") (pin "6") (pinfunction "A1_6") (pintype "passive"))
      (node (ref "J1") (pin "1") (pinfunction "S_1") (pintype "passive"))
      (node (ref "Q1") (pin "C") (pinfunction "C_C") (pintype "passive"))
    )
    (net (code "40") (name "REDPWM") (class "Default")
      (node (ref "C16") (pin "1") (pinfunction "1_1") (pintype "passive"))
      (node (ref "JP2") (pin "8") (pinfunction "8_8") (pintype "passive"))
      (node (ref "R6") (pin "2") (pinfunction "2_2") (pintype "passive"))
    )
    (net (code "41") (name "RX(DMX)") (class "Default")
      (node (ref "JP2") (pin "2") (pinfunction "2_2") (pintype "passive"))
      (node (ref "U3") (pin "4") (pinfunction "RXD_4") (pintype "bidirectional"))
    )
    (net (code "42") (name "TX(DMX)") (class "Default")
      (node (ref "JP2") (pin "3") (pinfunction "3_3") (pintype "passive"))
      (node (ref "U3") (pin "7") (pinfunction "TXD_7") (pintype "bidirectional"))
    )
    (net (code "43") (name "V+") (class "Default")
      (node (ref "C1") (pin "+") (pinfunction "+_+") (pintype "passive"))
      (node (ref "C17") (pin "1") (pinfunction "1_1") (pintype "passive"))
      (node (ref "D2") (pin "2") (pinfunction "K_2") (pintype "passive"))
      (node (ref "D2") (pin "5") (pinfunction "K_5") (pintype "passive"))
      (node (ref "F1") (pin "P$2") (pinfunction "2_P$2") (pintype "passive"))
      (node (ref "J1") (pin "5") (pinfunction "S_5") (pintype "passive"))
      (node (ref "U2") (pin "5") (pinfunction "VIN_5") (pintype "power_in"))
    )
    (net (code "44") (name "VCC") (class "Default")
      (node (ref "C3") (pin "1") (pinfunction "1_1") (pintype "passive"))
      (node (ref "C4") (pin "+") (pinfunction "+_+") (pintype "passive"))
      (node (ref "JP3") (pin "1") (pinfunction "1_1") (pintype "passive"))
      (node (ref "L1") (pin "P$1") (pinfunction "1_P$1") (pintype "passive"))
      (node (ref "R1") (pin "2") (pinfunction "2_2") (pintype "passive"))
    )
    (net (code "45") (name "WHITELED") (class "Default")
      (node (ref "D2") (pin "1") (pinfunction "A1_1") (pintype "passive"))
      (node (ref "J1") (pin "4") (pinfunction "S_4") (pintype "passive"))
      (node (ref "Q4") (pin "C") (pinfunction "C_C") (pintype "passive"))
    )
    (net (code "46") (name "WHITEPWM") (class "Default")
      (node (ref "C13") (pin "1") (pinfunction "1_1") (pintype "passive"))
      (node (ref "JP2") (pin "11") (pinfunction "11_11") (pintype "passive"))
      (node (ref "R3") (pin "2") (pinfunction "2_2") (pintype "passive"))
    )
    (net (code "47") (name "unconnected-(DMXA-4-Pad4A)") (class "Default")
      (node (ref "DMX") (pin "4A") (pinfunction "4_4A") (pintype "passive"))
    )
    (net (code "48") (name "unconnected-(DMXA-5-Pad5A)") (class "Default")
      (node (ref "DMX") (pin "5A") (pinfunction "5_5A") (pintype "passive"))
    )
    (net (code "49") (name "unconnected-(DMXA-6-Pad6A)") (class "Default")
      (node (ref "DMX") (pin "6A") (pinfunction "6_6A") (pintype "passive"))
    )
    (net (code "50") (name "unconnected-(DMXB-4-Pad4B)") (class "Default")
      (node (ref "DMX") (pin "4B") (pinfunction "4_4B") (pintype "passive"))
    )
    (net (code "51") (name "unconnected-(DMXB-5-Pad5B)") (class "Default")
      (node (ref "DMX") (pin "5B") (pinfunction "5_5B") (pintype "passive"))
    )
    (net (code "52") (name "unconnected-(DMXB-6-Pad6B)") (class "Default")
      (node (ref "DMX") (pin "6B") (pinfunction "6_6B") (pintype "passive"))
    )
    (net (code "53") (name "unconnected-(JP2-Pad4)") (class "Default")
      (node (ref "JP2") (pin "4") (pinfunction "4_4") (pintype "passive"))
    )
    (net (code "54") (name "unconnected-(JP2-Pad5)") (class "Default")
      (node (ref "JP2") (pin "5") (pinfunction "5_5") (pintype "passive"))
    )
    (net (code "55") (name "unconnected-(JP2-Pad6)") (class "Default")
      (node (ref "JP2") (pin "6") (pinfunction "6_6") (pintype "passive"))
    )
    (net (code "56") (name "unconnected-(JP2-Pad7)") (class "Default")
      (node (ref "JP2") (pin "7") (pinfunction "7_7") (pintype "passive"))
    )
    (net (code "57") (name "unconnected-(JP2-Pad12)") (class "Default")
      (node (ref "JP2") (pin "12") (pinfunction "12_12") (pintype "passive"))
    )
    (net (code "58") (name "unconnected-(JP2-Pad13)") (class "Default")
      (node (ref "JP2") (pin "13") (pinfunction "13_13") (pintype "passive"))
    )
    (net (code "59") (name "unconnected-(JP2-Pad14)") (class "Default")
      (node (ref "JP2") (pin "14") (pinfunction "14_14") (pintype "passive"))
    )
    (net (code "60") (name "unconnected-(JP3-Pad6)") (class "Default")
      (node (ref "JP3") (pin "6") (pinfunction "6_6") (pintype "passive"))
    )
    (net (code "61") (name "unconnected-(JP3-Pad7)") (class "Default")
      (node (ref "JP3") (pin "7") (pinfunction "7_7") (pintype "passive"))
    )
    (net (code "62") (name "unconnected-(JP3-Pad10)") (class "Default")
      (node (ref "JP3") (pin "10") (pinfunction "10_10") (pintype "passive"))
    )
    (net (code "63") (name "unconnected-(JP3-Pad14)") (class "Default")
      (node (ref "JP3") (pin "14") (pinfunction "14_14") (pintype "passive"))
    )
    (net (code "64") (name "unconnected-(JP4-Pad2)") (class "Default")
      (node (ref "JP4") (pin "2") (pinfunction "2_2") (pintype "passive"))
    )
    (net (code "65") (name "unconnected-(JP4-Pad5)") (class "Default")
      (node (ref "JP4") (pin "5") (pinfunction "5_5") (pintype "passive"))
    )
    (net (code "66") (name "unconnected-(U2-SHDN-Pad4)") (class "Default")
      (node (ref "U2") (pin "4") (pinfunction "SHDN_4") (pintype "input"))
    )
  )
)
